# AutoMOO_Schematic.net
KiCad netlist of a schematic drawn in Altium Designer
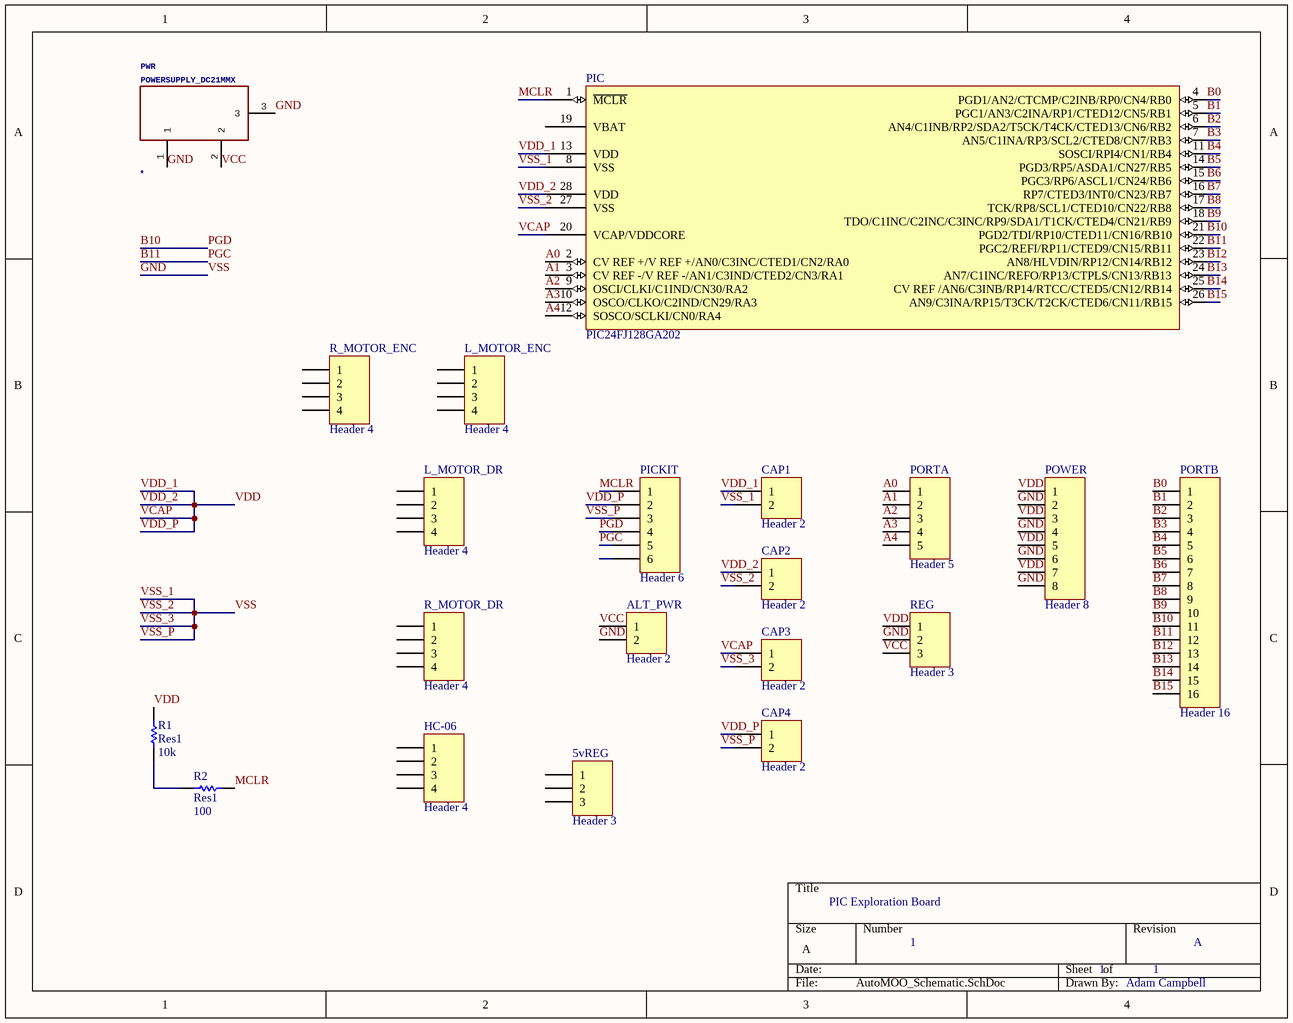
[diagram p0: AutoMOO_Schematic.SchDoc]

(export (version "E")
  (design (tool "Eeschema 10.0.6"))
  (components
    (comp (ref "5vREG")
      (value "Header 3")
      (footprint "HDR1X3")
      (description "Header, 3-Pin")
      (fields (field (name "PUBLISHER") "Altium Limited"))
      (libsource (lib "Miscellaneous Connectors") (part "Header 3"))
    )
    (comp (ref "ALT_PWR")
      (value "Header 2")
      (footprint "HDR1X2")
      (description "Header, 2-Pin")
      (fields (field (name "PUBLISHER") "Altium Limited"))
      (libsource (lib "Miscellaneous Connectors") (part "Header 2"))
    )
    (comp (ref "CAP1")
      (value "Header 2")
      (footprint "HDR1X2")
      (description "Header, 2-Pin")
      (fields (field (name "PUBLISHER") "Altium Limited"))
      (libsource (lib "Miscellaneous Connectors") (part "Header 2"))
    )
    (comp (ref "CAP2")
      (value "Header 2")
      (footprint "HDR1X2")
      (description "Header, 2-Pin")
      (fields (field (name "PUBLISHER") "Altium Limited"))
      (libsource (lib "Miscellaneous Connectors") (part "Header 2"))
    )
    (comp (ref "CAP3")
      (value "Header 2")
      (footprint "HDR1X2")
      (description "Header, 2-Pin")
      (fields (field (name "PUBLISHER") "Altium Limited"))
      (libsource (lib "Miscellaneous Connectors") (part "Header 2"))
    )
    (comp (ref "CAP4")
      (value "Header 2")
      (footprint "HDR1X2")
      (description "Header, 2-Pin")
      (fields (field (name "PUBLISHER") "Altium Limited"))
      (libsource (lib "Miscellaneous Connectors") (part "Header 2"))
    )
    (comp (ref "HC-06")
      (value "Header 4")
      (footprint "HDR1X4")
      (description "Header, 4-Pin")
      (fields (field (name "PUBLISHER") "Altium Limited"))
      (libsource (lib "Miscellaneous Connectors") (part "Header 4"))
    )
    (comp (ref "L_MOTOR_DR")
      (value "Header 4")
      (footprint "HDR1X4")
      (description "Header, 4-Pin")
      (fields (field (name "PUBLISHER") "Altium Limited"))
      (libsource (lib "Miscellaneous Connectors") (part "Header 4"))
    )
    (comp (ref "L_MOTOR_ENC")
      (value "Header 4")
      (footprint "HDR1X4")
      (description "Header, 4-Pin")
      (fields (field (name "PUBLISHER") "Altium Limited"))
      (libsource (lib "Miscellaneous Connectors") (part "Header 4"))
    )
    (comp (ref "PIC")
      (value "PIC24FJ128GA202")
      (footprint "SPDIP300-SP28")
      (libsource (lib "AutoMOO_Schematic_Library") (part "PIC24FJ128GA202"))
    )
    (comp (ref "PICKIT")
      (value "Header 6")
      (footprint "HDR1X6")
      (description "Header, 6-Pin")
      (fields (field (name "PUBLISHER") "Altium Limited"))
      (libsource (lib "Miscellaneous Connectors") (part "Header 6"))
    )
    (comp (ref "PORTA")
      (value "Header 5")
      (footprint "HDR1X5")
      (description "Header, 5-Pin")
      (fields (field (name "PUBLISHER") "Altium Limited"))
      (libsource (lib "Miscellaneous Connectors") (part "Header 5"))
    )
    (comp (ref "PORTB")
      (value "Header 16")
      (footprint "HDR1X16")
      (description "Header, 16-Pin")
      (fields (field (name "PUBLISHER") "Altium Limited"))
      (libsource (lib "Miscellaneous Connectors") (part "Header 16"))
    )
    (comp (ref "POWER")
      (value "Header 8")
      (footprint "HDR1X8")
      (description "Header, 8-Pin")
      (fields (field (name "PUBLISHER") "Altium Limited"))
      (libsource (lib "Miscellaneous Connectors") (part "Header 8"))
    )
    (comp (ref "PWR")
      (value "POWERSUPPLY_DC21MMX")
      (footprint "POWERSUPPLY")
      (fields (field (name "NAME") "*"))
      (libsource (lib "AutoMOO_Schematic_Library") (part "POWERSUPPLY"))
    )
    (comp (ref "R1")
      (value "Res1")
      (footprint "AXIAL-0.3")
      (description "Resistor")
      (fields (field (name "ALTIUM_VALUE") "10k") (field (name "PUBLISHER") "Altium Limited"))
      (libsource (lib "Miscellaneous Devices") (part "Res1"))
    )
    (comp (ref "R2")
      (value "Res1")
      (footprint "AXIAL-0.3")
      (description "Resistor")
      (fields (field (name "ALTIUM_VALUE") "100") (field (name "PUBLISHER") "Altium Limited"))
      (libsource (lib "Miscellaneous Devices") (part "Res1"))
    )
    (comp (ref "REG")
      (value "Header 3")
      (footprint "HDR1X3")
      (description "Header, 3-Pin")
      (fields (field (name "PUBLISHER") "Altium Limited"))
      (libsource (lib "Miscellaneous Connectors") (part "Header 3"))
    )
    (comp (ref "R_MOTOR_DR")
      (value "Header 4")
      (footprint "HDR1X4")
      (description "Header, 4-Pin")
      (fields (field (name "PUBLISHER") "Altium Limited"))
      (libsource (lib "Miscellaneous Connectors") (part "Header 4"))
    )
    (comp (ref "R_MOTOR_ENC")
      (value "Header 4")
      (footprint "HDR1X4")
      (description "Header, 4-Pin")
      (fields (field (name "PUBLISHER") "Altium Limited"))
      (libsource (lib "Miscellaneous Connectors") (part "Header 4"))
    )
  )
  (nets
    (net (code "1") (name "/A0") (class "Default")
      (node (ref "PIC") (pin "2") (pinfunction "CV_REF_+/V_REF_+/AN0/C3INC/CTED1/CN2/RA0_2") (pintype "bidirectional"))
      (node (ref "PORTA") (pin "1") (pinfunction "1_1") (pintype "passive"))
    )
    (net (code "2") (name "/A1") (class "Default")
      (node (ref "PIC") (pin "3") (pinfunction "CV_REF_-/V_REF_-/AN1/C3IND/CTED2/CN3/RA1_3") (pintype "bidirectional"))
      (node (ref "PORTA") (pin "2") (pinfunction "2_2") (pintype "passive"))
    )
    (net (code "3") (name "/A2") (class "Default")
      (node (ref "PIC") (pin "9") (pinfunction "OSCI/CLKI/C1IND/CN30/RA2_9") (pintype "bidirectional"))
      (node (ref "PORTA") (pin "3") (pinfunction "3_3") (pintype "passive"))
    )
    (net (code "4") (name "/A3") (class "Default")
      (node (ref "PIC") (pin "10") (pinfunction "OSCO/CLKO/C2IND/CN29/RA3_10") (pintype "bidirectional"))
      (node (ref "PORTA") (pin "4") (pinfunction "4_4") (pintype "passive"))
    )
    (net (code "5") (name "/A4") (class "Default")
      (node (ref "PIC") (pin "12") (pinfunction "SOSCO/SCLKI/CN0/RA4_12") (pintype "bidirectional"))
      (node (ref "PORTA") (pin "5") (pinfunction "5_5") (pintype "passive"))
    )
    (net (code "6") (name "/B0") (class "Default")
      (node (ref "PIC") (pin "4") (pinfunction "PGD1/AN2/CTCMP/C2INB/RP0/CN4/RB0_4") (pintype "bidirectional"))
      (node (ref "PORTB") (pin "1") (pinfunction "1_1") (pintype "passive"))
    )
    (net (code "7") (name "/B1") (class "Default")
      (node (ref "PIC") (pin "5") (pinfunction "PGC1/AN3/C2INA/RP1/CTED12/CN5/RB1_5") (pintype "bidirectional"))
      (node (ref "PORTB") (pin "2") (pinfunction "2_2") (pintype "passive"))
    )
    (net (code "8") (name "/B2") (class "Default")
      (node (ref "PIC") (pin "6") (pinfunction "AN4/C1INB/RP2/SDA2/T5CK/T4CK/CTED13/CN6/RB2_6") (pintype "bidirectional"))
      (node (ref "PORTB") (pin "3") (pinfunction "3_3") (pintype "passive"))
    )
    (net (code "9") (name "/B3") (class "Default")
      (node (ref "PIC") (pin "7") (pinfunction "AN5/C1INA/RP3/SCL2/CTED8/CN7/RB3_7") (pintype "bidirectional"))
      (node (ref "PORTB") (pin "4") (pinfunction "4_4") (pintype "passive"))
    )
    (net (code "10") (name "/B4") (class "Default")
      (node (ref "PIC") (pin "11") (pinfunction "SOSCI/RPI4/CN1/RB4_11") (pintype "bidirectional"))
      (node (ref "PORTB") (pin "5") (pinfunction "5_5") (pintype "passive"))
    )
    (net (code "11") (name "/B5") (class "Default")
      (node (ref "PIC") (pin "14") (pinfunction "PGD3/RP5/ASDA1/CN27/RB5_14") (pintype "bidirectional"))
      (node (ref "PORTB") (pin "6") (pinfunction "6_6") (pintype "passive"))
    )
    (net (code "12") (name "/B6") (class "Default")
      (node (ref "PIC") (pin "15") (pinfunction "PGC3/RP6/ASCL1/CN24/RB6_15") (pintype "bidirectional"))
      (node (ref "PORTB") (pin "7") (pinfunction "7_7") (pintype "passive"))
    )
    (net (code "13") (name "/B7") (class "Default")
      (node (ref "PIC") (pin "16") (pinfunction "RP7/CTED3/INT0/CN23/RB7_16") (pintype "bidirectional"))
      (node (ref "PORTB") (pin "8") (pinfunction "8_8") (pintype "passive"))
    )
    (net (code "14") (name "/B8") (class "Default")
      (node (ref "PIC") (pin "17") (pinfunction "TCK/RP8/SCL1/CTED10/CN22/RB8_17") (pintype "bidirectional"))
      (node (ref "PORTB") (pin "9") (pinfunction "9_9") (pintype "passive"))
    )
    (net (code "15") (name "/B9") (class "Default")
      (node (ref "PIC") (pin "18") (pinfunction "TDO/C1INC/C2INC/C3INC/RP9/SDA1/T1CK/CTED4/CN21/RB9_18") (pintype "bidirectional"))
      (node (ref "PORTB") (pin "10") (pinfunction "10_10") (pintype "passive"))
    )
    (net (code "16") (name "/B10") (class "Default")
      (node (ref "PIC") (pin "21") (pinfunction "PGD2/TDI/RP10/CTED11/CN16/RB10_21") (pintype "bidirectional"))
      (node (ref "PICKIT") (pin "4") (pinfunction "4_4") (pintype "passive"))
      (node (ref "PORTB") (pin "11") (pinfunction "11_11") (pintype "passive"))
    )
    (net (code "17") (name "/B11") (class "Default")
      (node (ref "PIC") (pin "22") (pinfunction "PGC2/REFI/RP11/CTED9/CN15/RB11_22") (pintype "bidirectional"))
      (node (ref "PICKIT") (pin "5") (pinfunction "5_5") (pintype "passive"))
      (node (ref "PORTB") (pin "12") (pinfunction "12_12") (pintype "passive"))
    )
    (net (code "18") (name "/B12") (class "Default")
      (node (ref "PIC") (pin "23") (pinfunction "AN8/HLVDIN/RP12/CN14/RB12_23") (pintype "bidirectional"))
      (node (ref "PORTB") (pin "13") (pinfunction "13_13") (pintype "passive"))
    )
    (net (code "19") (name "/B13") (class "Default")
      (node (ref "PIC") (pin "24") (pinfunction "AN7/C1INC/REFO/RP13/CTPLS/CN13/RB13_24") (pintype "bidirectional"))
      (node (ref "PORTB") (pin "14") (pinfunction "14_14") (pintype "passive"))
    )
    (net (code "20") (name "/B14") (class "Default")
      (node (ref "PIC") (pin "25") (pinfunction "CV_REF_/AN6/C3INB/RP14/RTCC/CTED5/CN12/RB14_25") (pintype "bidirectional"))
      (node (ref "PORTB") (pin "15") (pinfunction "15_15") (pintype "passive"))
    )
    (net (code "21") (name "/B15") (class "Default")
      (node (ref "PIC") (pin "26") (pinfunction "AN9/C3INA/RP15/T3CK/T2CK/CTED6/CN11/RB15_26") (pintype "bidirectional"))
      (node (ref "PORTB") (pin "16") (pinfunction "16_16") (pintype "passive"))
    )
    (net (code "22") (name "/GND") (class "Default")
      (node (ref "ALT_PWR") (pin "2") (pinfunction "2_2") (pintype "passive"))
      (node (ref "CAP1") (pin "2") (pinfunction "2_2") (pintype "passive"))
      (node (ref "CAP2") (pin "2") (pinfunction "2_2") (pintype "passive"))
      (node (ref "CAP3") (pin "2") (pinfunction "2_2") (pintype "passive"))
      (node (ref "CAP4") (pin "2") (pinfunction "2_2") (pintype "passive"))
      (node (ref "PIC") (pin "27") (pinfunction "VSS_27") (pintype "power_in"))
      (node (ref "PIC") (pin "8") (pinfunction "VSS_8") (pintype "power_in"))
      (node (ref "PICKIT") (pin "3") (pinfunction "3_3") (pintype "passive"))
      (node (ref "POWER") (pin "2") (pinfunction "2_2") (pintype "passive"))
      (node (ref "POWER") (pin "4") (pinfunction "4_4") (pintype "passive"))
      (node (ref "POWER") (pin "6") (pinfunction "6_6") (pintype "passive"))
      (node (ref "POWER") (pin "8") (pinfunction "8_8") (pintype "passive"))
      (node (ref "PWR") (pin "1") (pinfunction "1_1") (pintype "power_in"))
      (node (ref "PWR") (pin "3") (pinfunction "3_3") (pintype "power_in"))
      (node (ref "REG") (pin "2") (pinfunction "2_2") (pintype "passive"))
    )
    (net (code "23") (name "/MCLR") (class "Default")
      (node (ref "PIC") (pin "1") (pinfunction "~{MCLR}_1") (pintype "bidirectional"))
      (node (ref "PICKIT") (pin "1") (pinfunction "1_1") (pintype "passive"))
      (node (ref "R2") (pin "2") (pinfunction "2_2") (pintype "passive"))
    )
    (net (code "24") (name "/VCAP") (class "Default")
      (node (ref "CAP1") (pin "1") (pinfunction "1_1") (pintype "passive"))
      (node (ref "CAP2") (pin "1") (pinfunction "1_1") (pintype "passive"))
      (node (ref "CAP3") (pin "1") (pinfunction "1_1") (pintype "passive"))
      (node (ref "CAP4") (pin "1") (pinfunction "1_1") (pintype "passive"))
      (node (ref "PIC") (pin "13") (pinfunction "VDD_13") (pintype "power_in"))
      (node (ref "PIC") (pin "20") (pinfunction "VCAP/VDDCORE_20") (pintype "power_in"))
      (node (ref "PIC") (pin "28") (pinfunction "VDD_28") (pintype "power_in"))
      (node (ref "PICKIT") (pin "2") (pinfunction "2_2") (pintype "passive"))
      (node (ref "POWER") (pin "1") (pinfunction "1_1") (pintype "passive"))
      (node (ref "POWER") (pin "3") (pinfunction "3_3") (pintype "passive"))
      (node (ref "POWER") (pin "5") (pinfunction "5_5") (pintype "passive"))
      (node (ref "POWER") (pin "7") (pinfunction "7_7") (pintype "passive"))
      (node (ref "R1") (pin "2") (pinfunction "2_2") (pintype "passive"))
      (node (ref "REG") (pin "1") (pinfunction "1_1") (pintype "passive"))
    )
    (net (code "25") (name "/VCC") (class "Default")
      (node (ref "ALT_PWR") (pin "1") (pinfunction "1_1") (pintype "passive"))
      (node (ref "PWR") (pin "2") (pinfunction "2_2") (pintype "power_in"))
      (node (ref "REG") (pin "3") (pinfunction "3_3") (pintype "passive"))
    )
    (net (code "26") (name "Net-(R1-Pad1)") (class "Default")
      (node (ref "R1") (pin "1") (pinfunction "1_1") (pintype "passive"))
      (node (ref "R2") (pin "1") (pinfunction "1_1") (pintype "passive"))
    )
    (net (code "27") (name "unconnected-(5vREG-Pad1)") (class "Default")
      (node (ref "5vREG") (pin "1") (pinfunction "1_1") (pintype "passive"))
    )
    (net (code "28") (name "unconnected-(5vREG-Pad2)") (class "Default")
      (node (ref "5vREG") (pin "2") (pinfunction "2_2") (pintype "passive"))
    )
    (net (code "29") (name "unconnected-(5vREG-Pad3)") (class "Default")
      (node (ref "5vREG") (pin "3") (pinfunction "3_3") (pintype "passive"))
    )
    (net (code "30") (name "unconnected-(HC-06-Pad1)") (class "Default")
      (node (ref "HC-06") (pin "1") (pinfunction "1_1") (pintype "passive"))
    )
    (net (code "31") (name "unconnected-(HC-06-Pad2)") (class "Default")
      (node (ref "HC-06") (pin "2") (pinfunction "2_2") (pintype "passive"))
    )
    (net (code "32") (name "unconnected-(HC-06-Pad3)") (class "Default")
      (node (ref "HC-06") (pin "3") (pinfunction "3_3") (pintype "passive"))
    )
    (net (code "33") (name "unconnected-(HC-06-Pad4)") (class "Default")
      (node (ref "HC-06") (pin "4") (pinfunction "4_4") (pintype "passive"))
    )
    (net (code "34") (name "unconnected-(L_MOTOR_DR-Pad1)") (class "Default")
      (node (ref "L_MOTOR_DR") (pin "1") (pinfunction "1_1") (pintype "passive"))
    )
    (net (code "35") (name "unconnected-(L_MOTOR_DR-Pad2)") (class "Default")
      (node (ref "L_MOTOR_DR") (pin "2") (pinfunction "2_2") (pintype "passive"))
    )
    (net (code "36") (name "unconnected-(L_MOTOR_DR-Pad3)") (class "Default")
      (node (ref "L_MOTOR_DR") (pin "3") (pinfunction "3_3") (pintype "passive"))
    )
    (net (code "37") (name "unconnected-(L_MOTOR_DR-Pad4)") (class "Default")
      (node (ref "L_MOTOR_DR") (pin "4") (pinfunction "4_4") (pintype "passive"))
    )
    (net (code "38") (name "unconnected-(L_MOTOR_ENC-Pad1)") (class "Default")
      (node (ref "L_MOTOR_ENC") (pin "1") (pinfunction "1_1") (pintype "passive"))
    )
    (net (code "39") (name "unconnected-(L_MOTOR_ENC-Pad2)") (class "Default")
      (node (ref "L_MOTOR_ENC") (pin "2") (pinfunction "2_2") (pintype "passive"))
    )
    (net (code "40") (name "unconnected-(L_MOTOR_ENC-Pad3)") (class "Default")
      (node (ref "L_MOTOR_ENC") (pin "3") (pinfunction "3_3") (pintype "passive"))
    )
    (net (code "41") (name "unconnected-(L_MOTOR_ENC-Pad4)") (class "Default")
      (node (ref "L_MOTOR_ENC") (pin "4") (pinfunction "4_4") (pintype "passive"))
    )
    (net (code "42") (name "unconnected-(PIC-VBAT-Pad19)") (class "Default")
      (node (ref "PIC") (pin "19") (pinfunction "VBAT_19") (pintype "passive"))
    )
    (net (code "43") (name "unconnected-(PICKIT-Pad6)") (class "Default")
      (node (ref "PICKIT") (pin "6") (pinfunction "6_6") (pintype "passive"))
    )
    (net (code "44") (name "unconnected-(R_MOTOR_DR-Pad1)") (class "Default")
      (node (ref "R_MOTOR_DR") (pin "1") (pinfunction "1_1") (pintype "passive"))
    )
    (net (code "45") (name "unconnected-(R_MOTOR_DR-Pad2)") (class "Default")
      (node (ref "R_MOTOR_DR") (pin "2") (pinfunction "2_2") (pintype "passive"))
    )
    (net (code "46") (name "unconnected-(R_MOTOR_DR-Pad3)") (class "Default")
      (node (ref "R_MOTOR_DR") (pin "3") (pinfunction "3_3") (pintype "passive"))
    )
    (net (code "47") (name "unconnected-(R_MOTOR_DR-Pad4)") (class "Default")
      (node (ref "R_MOTOR_DR") (pin "4") (pinfunction "4_4") (pintype "passive"))
    )
    (net (code "48") (name "unconnected-(R_MOTOR_ENC-Pad1)") (class "Default")
      (node (ref "R_MOTOR_ENC") (pin "1") (pinfunction "1_1") (pintype "passive"))
    )
    (net (code "49") (name "unconnected-(R_MOTOR_ENC-Pad2)") (class "Default")
      (node (ref "R_MOTOR_ENC") (pin "2") (pinfunction "2_2") (pintype "passive"))
    )
    (net (code "50") (name "unconnected-(R_MOTOR_ENC-Pad3)") (class "Default")
      (node (ref "R_MOTOR_ENC") (pin "3") (pinfunction "3_3") (pintype "passive"))
    )
    (net (code "51") (name "unconnected-(R_MOTOR_ENC-Pad4)") (class "Default")
      (node (ref "R_MOTOR_ENC") (pin "4") (pinfunction "4_4") (pintype "passive"))
    )
  )
)
